# Sheet1.net
KiCad netlist of a schematic drawn in Altium Designer
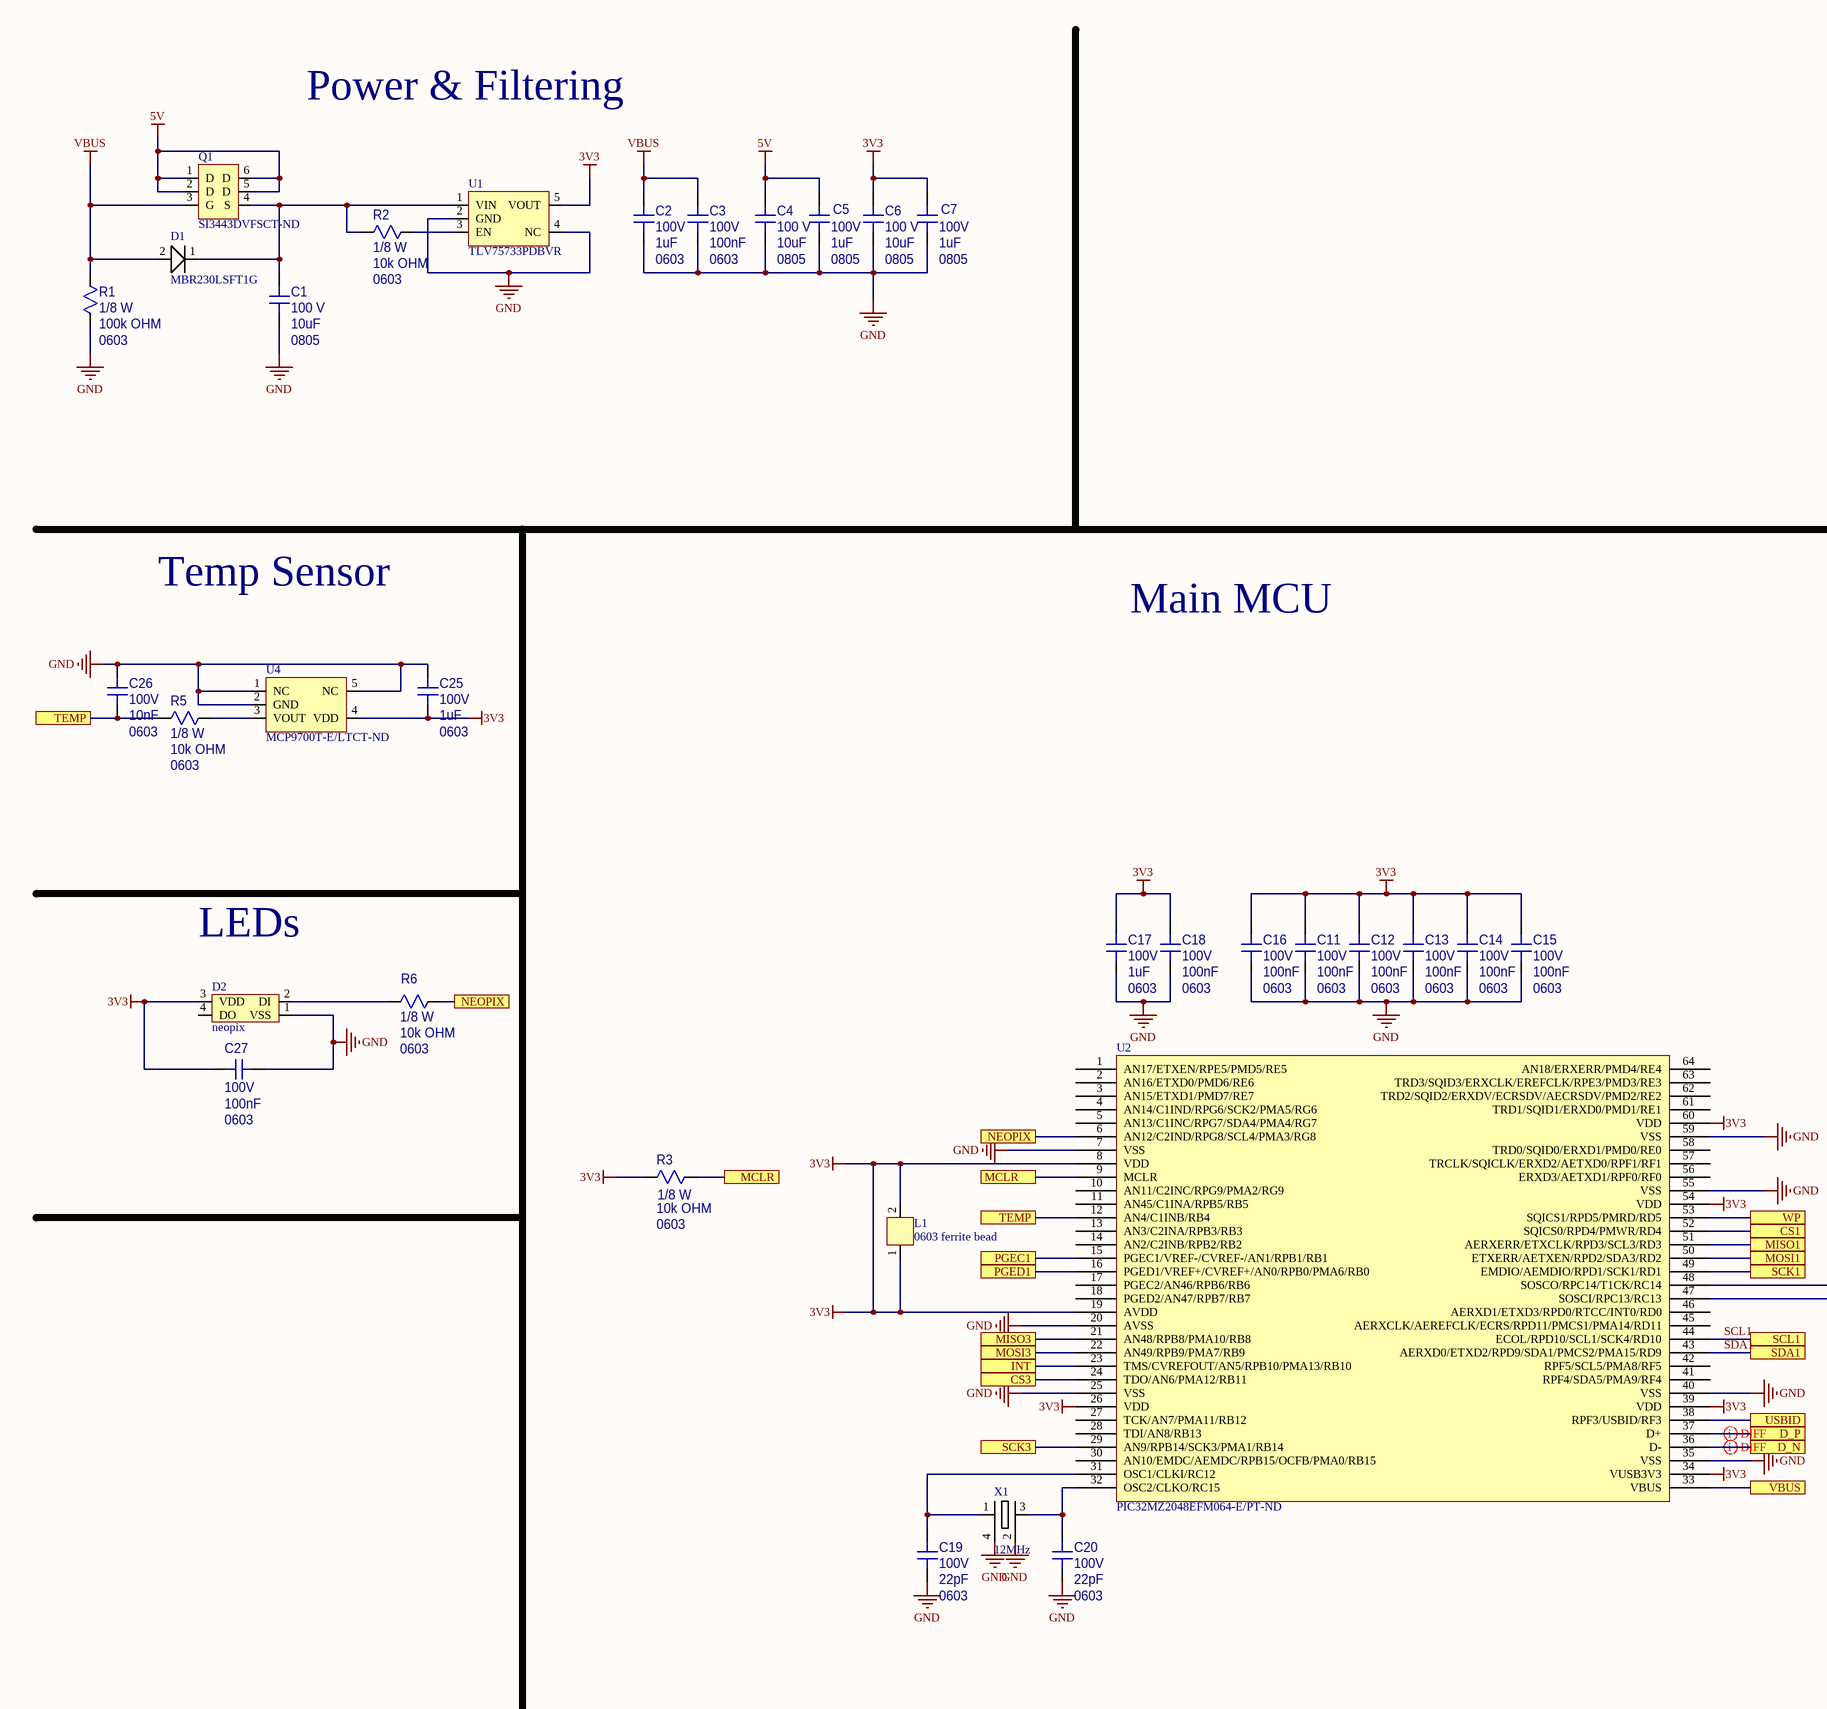
[diagram p0: Sheet1.SchDoc, left]
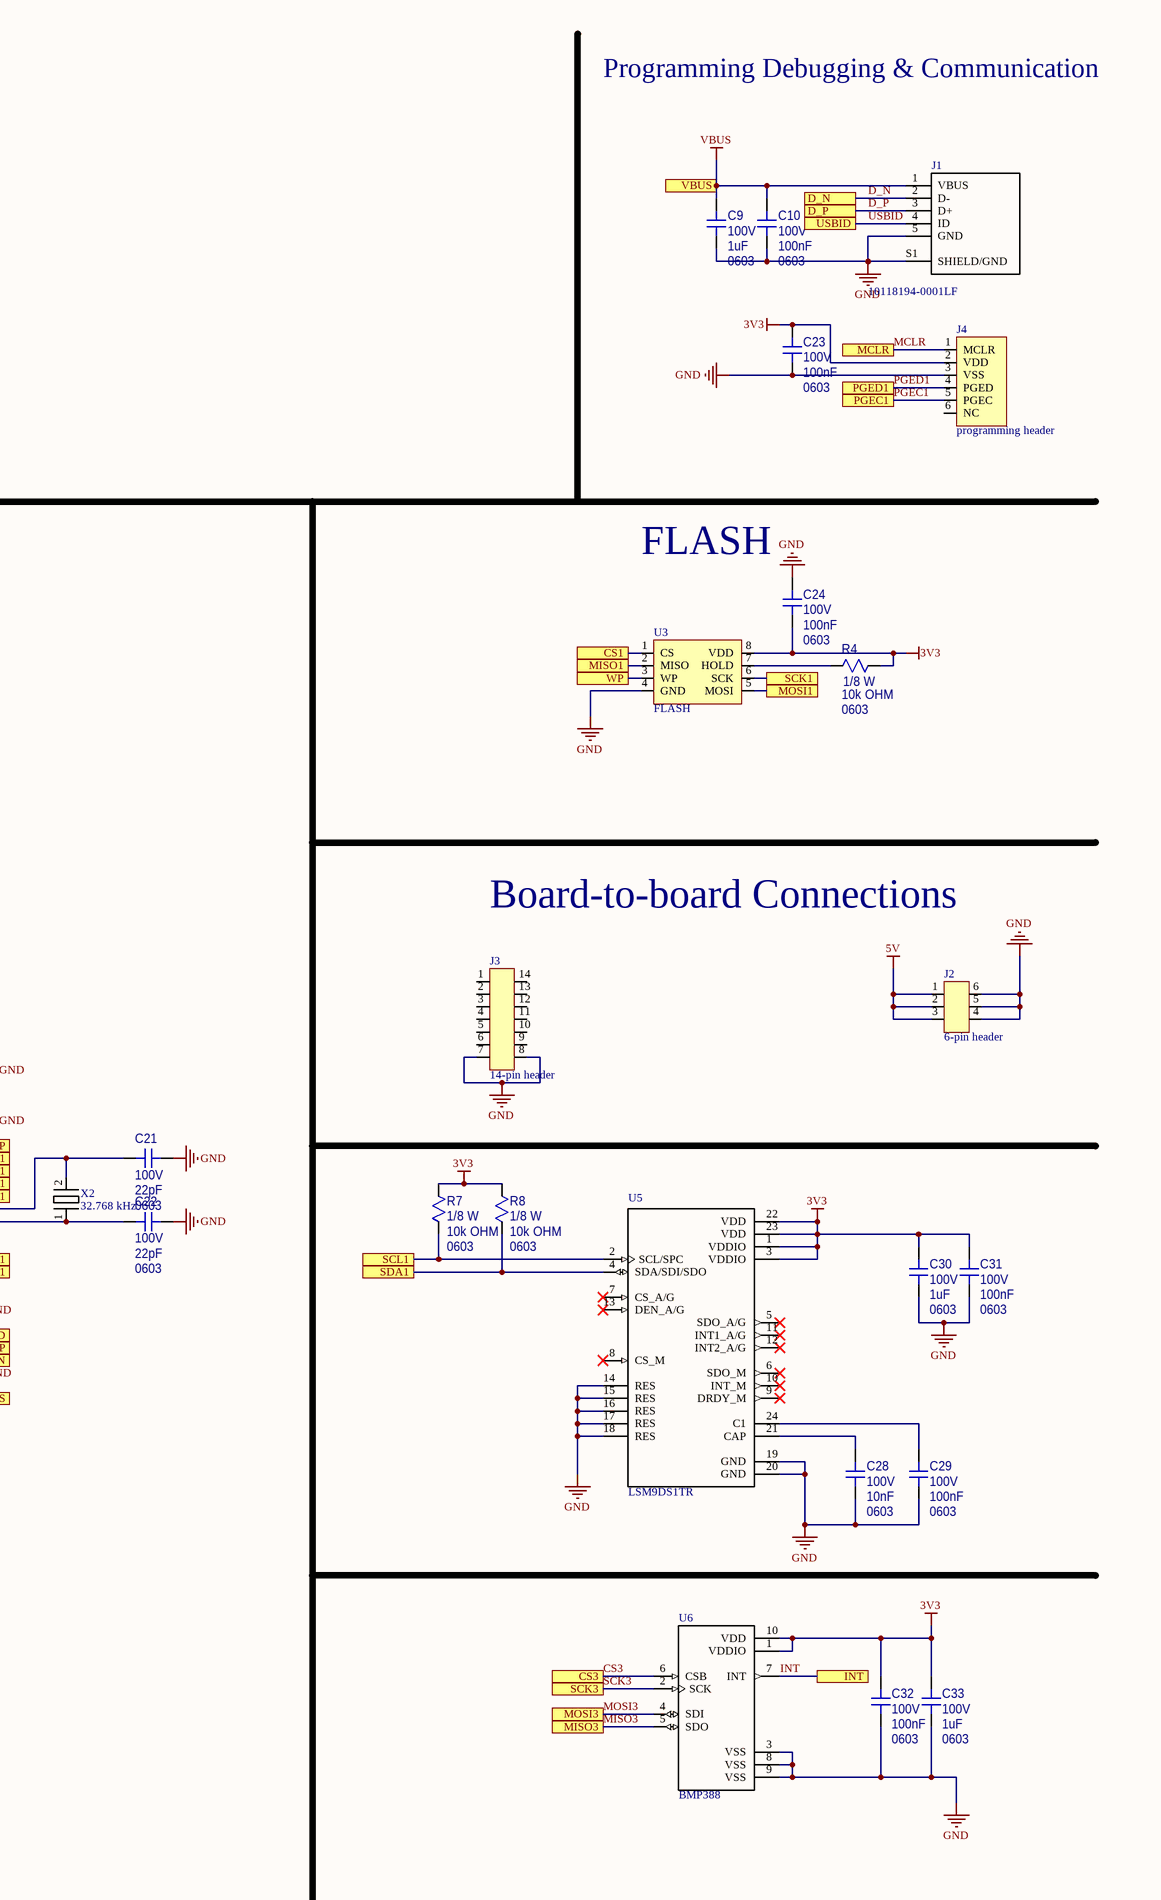
[diagram p1: Sheet1.SchDoc, right]

(export (version "E")
  (design (tool "Eeschema 10.0.6"))
  (components
    (comp (ref "C1")
      (value "10uF")
      (footprint "0805C (reflow)")
      (description "Default 0805 capacitor")
      (fields
        (field (name "VOLTAGE") "100 V")
        (field (name "SIZE") "0805")
        (field (name "Comment") "Capacitor")
      )
      (libsource (lib "rocket_mcu") (part "0805 Capacitor"))
    )
    (comp (ref "C2")
      (value "1uF")
      (footprint "0603C (reflow)")
      (description "Default 0603 capacitor")
      (fields
        (field (name "VOLTAGE") "100V")
        (field (name "SIZE") "0603")
        (field (name "Comment") "Capacitor")
      )
      (libsource (lib "rocket_mcu") (part "0603 Capacitor"))
    )
    (comp (ref "C3")
      (value "100nF")
      (footprint "0603C (reflow)")
      (description "Default 0603 capacitor")
      (fields
        (field (name "VOLTAGE") "100V")
        (field (name "SIZE") "0603")
        (field (name "Comment") "Capacitor")
      )
      (libsource (lib "rocket_mcu") (part "0603 Capacitor"))
    )
    (comp (ref "C4")
      (value "10uF")
      (footprint "0805C (reflow)")
      (description "Default 0805 capacitor")
      (fields
        (field (name "VOLTAGE") "100 V")
        (field (name "SIZE") "0805")
        (field (name "Comment") "Capacitor")
      )
      (libsource (lib "rocket_mcu") (part "0805 Capacitor"))
    )
    (comp (ref "C5")
      (value "1uF")
      (footprint "0805C (reflow)")
      (description "Default 0805 capacitor")
      (fields
        (field (name "VOLTAGE") "100V")
        (field (name "SIZE") "0805")
        (field (name "Comment") "Capacitor")
      )
      (libsource (lib "rocket_mcu") (part "0805 Capacitor"))
    )
    (comp (ref "C6")
      (value "10uF")
      (footprint "0805C (reflow)")
      (description "Default 0805 capacitor")
      (fields
        (field (name "VOLTAGE") "100 V")
        (field (name "SIZE") "0805")
        (field (name "Comment") "Capacitor")
      )
      (libsource (lib "rocket_mcu") (part "0805 Capacitor"))
    )
    (comp (ref "C7")
      (value "1uF")
      (footprint "0805C (reflow)")
      (description "Default 0805 capacitor")
      (fields
        (field (name "VOLTAGE") "100V")
        (field (name "SIZE") "0805")
        (field (name "Comment") "Capacitor")
      )
      (libsource (lib "rocket_mcu") (part "0805 Capacitor"))
    )
    (comp (ref "C9")
      (value "1uF")
      (footprint "0603C (reflow)")
      (description "Default 0603 capacitor")
      (fields
        (field (name "VOLTAGE") "100V")
        (field (name "SIZE") "0603")
        (field (name "Comment") "Capacitor")
      )
      (libsource (lib "rocket_mcu") (part "0603 Capacitor"))
    )
    (comp (ref "C10")
      (value "100nF")
      (footprint "0603C (reflow)")
      (description "Default 0603 capacitor")
      (fields
        (field (name "VOLTAGE") "100V")
        (field (name "SIZE") "0603")
        (field (name "Comment") "Capacitor")
      )
      (libsource (lib "rocket_mcu") (part "0603 Capacitor"))
    )
    (comp (ref "C11")
      (value "100nF")
      (footprint "0603C (reflow)")
      (description "Default 0603 capacitor")
      (fields
        (field (name "VOLTAGE") "100V")
        (field (name "SIZE") "0603")
        (field (name "Comment") "Capacitor")
      )
      (libsource (lib "rocket_mcu") (part "0603 Capacitor"))
    )
    (comp (ref "C12")
      (value "100nF")
      (footprint "0603C (reflow)")
      (description "Default 0603 capacitor")
      (fields
        (field (name "VOLTAGE") "100V")
        (field (name "SIZE") "0603")
        (field (name "Comment") "Capacitor")
      )
      (libsource (lib "rocket_mcu") (part "0603 Capacitor"))
    )
    (comp (ref "C13")
      (value "100nF")
      (footprint "0603C (reflow)")
      (description "Default 0603 capacitor")
      (fields
        (field (name "VOLTAGE") "100V")
        (field (name "SIZE") "0603")
        (field (name "Comment") "Capacitor")
      )
      (libsource (lib "rocket_mcu") (part "0603 Capacitor"))
    )
    (comp (ref "C14")
      (value "100nF")
      (footprint "0603C (reflow)")
      (description "Default 0603 capacitor")
      (fields
        (field (name "VOLTAGE") "100V")
        (field (name "SIZE") "0603")
        (field (name "Comment") "Capacitor")
      )
      (libsource (lib "rocket_mcu") (part "0603 Capacitor"))
    )
    (comp (ref "C15")
      (value "100nF")
      (footprint "0603C (reflow)")
      (description "Default 0603 capacitor")
      (fields
        (field (name "VOLTAGE") "100V")
        (field (name "SIZE") "0603")
        (field (name "Comment") "Capacitor")
      )
      (libsource (lib "rocket_mcu") (part "0603 Capacitor"))
    )
    (comp (ref "C16")
      (value "100nF")
      (footprint "0603C (reflow)")
      (description "Default 0603 capacitor")
      (fields
        (field (name "VOLTAGE") "100V")
        (field (name "SIZE") "0603")
        (field (name "Comment") "Capacitor")
      )
      (libsource (lib "rocket_mcu") (part "0603 Capacitor"))
    )
    (comp (ref "C17")
      (value "1uF")
      (footprint "0603C (reflow)")
      (description "Default 0603 capacitor")
      (fields
        (field (name "VOLTAGE") "100V")
        (field (name "SIZE") "0603")
        (field (name "Comment") "Capacitor")
      )
      (libsource (lib "rocket_mcu") (part "0603 Capacitor"))
    )
    (comp (ref "C18")
      (value "100nF")
      (footprint "0603C (reflow)")
      (description "Default 0603 capacitor")
      (fields
        (field (name "VOLTAGE") "100V")
        (field (name "SIZE") "0603")
        (field (name "Comment") "Capacitor")
      )
      (libsource (lib "rocket_mcu") (part "0603 Capacitor"))
    )
    (comp (ref "C19")
      (value "22pF")
      (footprint "0603C (reflow)")
      (description "Default 0603 capacitor")
      (fields
        (field (name "VOLTAGE") "100V")
        (field (name "SIZE") "0603")
        (field (name "Comment") "Capacitor")
      )
      (libsource (lib "rocket_mcu") (part "0603 Capacitor"))
    )
    (comp (ref "C20")
      (value "22pF")
      (footprint "0603C (reflow)")
      (description "Default 0603 capacitor")
      (fields
        (field (name "VOLTAGE") "100V")
        (field (name "SIZE") "0603")
        (field (name "Comment") "Capacitor")
      )
      (libsource (lib "rocket_mcu") (part "0603 Capacitor"))
    )
    (comp (ref "C21")
      (value "22pF")
      (footprint "0603C (reflow)")
      (description "Default 0603 capacitor")
      (fields
        (field (name "VOLTAGE") "100V")
        (field (name "SIZE") "0603")
        (field (name "Comment") "Capacitor")
      )
      (libsource (lib "rocket_mcu") (part "0603 Capacitor"))
    )
    (comp (ref "C22")
      (value "22pF")
      (footprint "0603C (reflow)")
      (description "Default 0603 capacitor")
      (fields
        (field (name "VOLTAGE") "100V")
        (field (name "SIZE") "0603")
        (field (name "Comment") "Capacitor")
      )
      (libsource (lib "rocket_mcu") (part "0603 Capacitor"))
    )
    (comp (ref "C23")
      (value "100nF")
      (footprint "0603C (reflow)")
      (description "Default 0603 capacitor")
      (fields
        (field (name "VOLTAGE") "100V")
        (field (name "SIZE") "0603")
        (field (name "Comment") "Capacitor")
      )
      (libsource (lib "rocket_mcu") (part "0603 Capacitor"))
    )
    (comp (ref "C24")
      (value "100nF")
      (footprint "0603C (reflow)")
      (description "Default 0603 capacitor")
      (fields
        (field (name "VOLTAGE") "100V")
        (field (name "SIZE") "0603")
        (field (name "Comment") "Capacitor")
      )
      (libsource (lib "rocket_mcu") (part "0603 Capacitor"))
    )
    (comp (ref "C25")
      (value "1uF")
      (footprint "0603C (reflow)")
      (description "Default 0603 capacitor")
      (fields
        (field (name "VOLTAGE") "100V")
        (field (name "SIZE") "0603")
        (field (name "Comment") "Capacitor")
      )
      (libsource (lib "rocket_mcu") (part "0603 Capacitor"))
    )
    (comp (ref "C26")
      (value "10nF")
      (footprint "0603C (reflow)")
      (description "Default 0603 capacitor")
      (fields
        (field (name "VOLTAGE") "100V")
        (field (name "SIZE") "0603")
        (field (name "Comment") "Capacitor")
      )
      (libsource (lib "rocket_mcu") (part "0603 Capacitor"))
    )
    (comp (ref "C27")
      (value "100nF")
      (footprint "0603C (reflow)")
      (description "Default 0603 capacitor")
      (fields
        (field (name "VOLTAGE") "100V")
        (field (name "SIZE") "0603")
        (field (name "Comment") "Capacitor")
      )
      (libsource (lib "rocket_mcu") (part "0603 Capacitor"))
    )
    (comp (ref "C28")
      (value "10nF")
      (footprint "0603C (reflow)")
      (description "Default 0603 capacitor")
      (fields
        (field (name "VOLTAGE") "100V")
        (field (name "SIZE") "0603")
        (field (name "Comment") "Capacitor")
      )
      (libsource (lib "rocket_mcu") (part "0603 Capacitor"))
    )
    (comp (ref "C29")
      (value "100nF")
      (footprint "0603C (reflow)")
      (description "Default 0603 capacitor")
      (fields
        (field (name "VOLTAGE") "100V")
        (field (name "SIZE") "0603")
        (field (name "Comment") "Capacitor")
      )
      (libsource (lib "rocket_mcu") (part "0603 Capacitor"))
    )
    (comp (ref "C30")
      (value "1uF")
      (footprint "0603C (reflow)")
      (description "Default 0603 capacitor")
      (fields
        (field (name "VOLTAGE") "100V")
        (field (name "SIZE") "0603")
        (field (name "Comment") "Capacitor")
      )
      (libsource (lib "rocket_mcu") (part "0603 Capacitor"))
    )
    (comp (ref "C31")
      (value "100nF")
      (footprint "0603C (reflow)")
      (description "Default 0603 capacitor")
      (fields
        (field (name "VOLTAGE") "100V")
        (field (name "SIZE") "0603")
        (field (name "Comment") "Capacitor")
      )
      (libsource (lib "rocket_mcu") (part "0603 Capacitor"))
    )
    (comp (ref "C32")
      (value "100nF")
      (footprint "0603C (reflow)")
      (description "Default 0603 capacitor")
      (fields
        (field (name "VOLTAGE") "100V")
        (field (name "SIZE") "0603")
        (field (name "Comment") "Capacitor")
      )
      (libsource (lib "rocket_mcu") (part "0603 Capacitor"))
    )
    (comp (ref "C33")
      (value "1uF")
      (footprint "0603C (reflow)")
      (description "Default 0603 capacitor")
      (fields
        (field (name "VOLTAGE") "100V")
        (field (name "SIZE") "0603")
        (field (name "Comment") "Capacitor")
      )
      (libsource (lib "rocket_mcu") (part "0603 Capacitor"))
    )
    (comp (ref "D1")
      (value "MBR230LSFT1G")
      (footprint "MBR230LSFT1G")
      (description "Schottky 30V 2A")
      (libsource (lib "rocket_mcu") (part "MBR230LSFT1G"))
    )
    (comp (ref "D2") (value "neopix") (footprint "neopix") (libsource (lib "rocket_mcu") (part "neopix")))
    (comp (ref "J1")
      (value "10118194-0001LF")
      (footprint "*AMPHENOL_10118194-0001LF_10118194-0001LF(Primary)")
      (description "USB - micro B USB 2.0 Receptacle Connector 5 Position Surface Mount, Right Angle; Through Hole")
      (fields (field (name "MF") "Amphenol ICC") (field (name "DIGI-KEY_PART_NUMBER") "609-4618-1-ND"))
      (libsource (lib "rocket_mcu") (part "10118194-0001LF"))
    )
    (comp (ref "J2")
      (value "6-pin header")
      (footprint "6-pin header")
      (libsource (lib "rocket_mcu") (part "6-pin header"))
    )
    (comp (ref "J3")
      (value "14-pin header")
      (footprint "14-pin header")
      (libsource (lib "rocket_mcu") (part "14-pin header"))
    )
    (comp (ref "J4")
      (value "programming header")
      (footprint "programming header")
      (libsource (lib "rocket_mcu") (part "programming header"))
    )
    (comp (ref "L1")
      (value "0603 ferrite bead")
      (footprint "0603R (reflow)")
      (libsource (lib "rocket_mcu") (part "0603 ferrite bead"))
    )
    (comp (ref "Q1")
      (value "SI3443DVFSCT-ND")
      (footprint "SI3443DVFSCT-ND")
      (libsource (lib "rocket_mcu") (part "SI3443DVFSCT-ND"))
    )
    (comp (ref "R1")
      (value "100k OHM")
      (footprint "0603R (reflow)")
      (description "Default 0603 resistor")
      (fields (field (name "POWER") "1/8 W") (field (name "SIZE") "0603") (field (name "Comment") "Resistor"))
      (libsource (lib "rocket_mcu") (part "0603 Resistor"))
    )
    (comp (ref "R2")
      (value "10k OHM")
      (footprint "0603R (reflow)")
      (description "Default 0603 resistor")
      (fields (field (name "POWER") "1/8 W") (field (name "SIZE") "0603") (field (name "Comment") "Resistor"))
      (libsource (lib "rocket_mcu") (part "0603 Resistor"))
    )
    (comp (ref "R3")
      (value "10k OHM")
      (footprint "0603R (reflow)")
      (description "Default 0603 resistor")
      (fields (field (name "POWER") "1/8 W") (field (name "SIZE") "0603") (field (name "Comment") "Resistor"))
      (libsource (lib "rocket_mcu") (part "0603 Resistor"))
    )
    (comp (ref "R4")
      (value "10k OHM")
      (footprint "0603R (reflow)")
      (description "Default 0603 resistor")
      (fields (field (name "POWER") "1/8 W") (field (name "SIZE") "0603") (field (name "Comment") "Resistor"))
      (libsource (lib "rocket_mcu") (part "0603 Resistor"))
    )
    (comp (ref "R5")
      (value "10k OHM")
      (footprint "0603R (reflow)")
      (description "Default 0603 resistor")
      (fields (field (name "POWER") "1/8 W") (field (name "SIZE") "0603") (field (name "Comment") "Resistor"))
      (libsource (lib "rocket_mcu") (part "0603 Resistor"))
    )
    (comp (ref "R6")
      (value "10k OHM")
      (footprint "0603R (reflow)")
      (description "Default 0603 resistor")
      (fields (field (name "POWER") "1/8 W") (field (name "SIZE") "0603") (field (name "Comment") "Resistor"))
      (libsource (lib "rocket_mcu") (part "0603 Resistor"))
    )
    (comp (ref "R7")
      (value "10k OHM")
      (footprint "0603R (reflow)")
      (description "Default 0603 resistor")
      (fields (field (name "POWER") "1/8 W") (field (name "SIZE") "0603") (field (name "Comment") "Resistor"))
      (libsource (lib "rocket_mcu") (part "0603 Resistor"))
    )
    (comp (ref "R8")
      (value "10k OHM")
      (footprint "0603R (reflow)")
      (description "Default 0603 resistor")
      (fields (field (name "POWER") "1/8 W") (field (name "SIZE") "0603") (field (name "Comment") "Resistor"))
      (libsource (lib "rocket_mcu") (part "0603 Resistor"))
    )
    (comp (ref "U1")
      (value "TLV75733PDBVR")
      (footprint "SOT23-5N")
      (libsource (lib "rocket_mcu") (part "TLV75733PDBVR"))
    )
    (comp (ref "U2")
      (value "PIC32MZ2048EFM064-E/PT-ND")
      (footprint "TQFP-64")
      (libsource (lib "rocket_mcu") (part "PIC32MZ2048EFM064-E/PT-ND"))
    )
    (comp (ref "U3") (value "FLASH") (footprint "8-SOIC") (libsource (lib "rocket_mcu") (part "MB85RS64V")))
    (comp (ref "U4")
      (value "MCP9700T-E/LTCT-ND")
      (footprint "MCP9700T-E/LT")
      (description "Temp sens")
      (libsource (lib "rocket_mcu") (part "MCP9700T-E/LTCT-ND"))
    )
    (comp (ref "U5")
      (value "LSM9DS1TR")
      (footprint "*PQFN43P300X350X102-24N")
      (description "Accelerometer, Gyroscope, Magnetometer, Temperature, 9 Axis Sensor I虏C, SPI Output")
      (fields (field (name "DIGI-KEY_PART_NUMBER") "497-14946-1-ND") (field (name "MF") "STMicroelectronics"))
      (libsource (lib "rocket_mcu") (part "LSM9DS1TR"))
    )
    (comp (ref "U6")
      (value "BMP388")
      (footprint "*PQFN50P200X200X80-10N")
      (description "Pressure Sensor 4.35PSI ~ 18.13PSI _30kPa ~ 125kPa_ Absolute 10-WFLGA")
      (fields (field (name "MF") "Bosch Sensortec") (field (name "DIGI-KEY_PART_NUMBER") "828-1079-1-ND"))
      (libsource (lib "rocket_mcu") (part "BMP388"))
    )
    (comp (ref "X1")
      (value "12MHz")
      (footprint "XC2731CT-ND")
      (libsource (lib "rocket_mcu") (part "XC2731CT-ND"))
    )
    (comp (ref "X2")
      (value "32.768 kHz")
      (footprint "XC2292CT-ND")
      (libsource (lib "rocket_mcu") (part "XC2292CT-ND"))
    )
  )
  (nets
    (net (code "1") (name "/CS1") (class "Default")
      (node (ref "U2") (pin "52") (pinfunction "SQICS0/RPD4/PMWR/RD4_52") (pintype "passive"))
      (node (ref "U3") (pin "1") (pinfunction "CS_1") (pintype "passive"))
    )
    (net (code "2") (name "/CS3") (class "Default")
      (node (ref "U2") (pin "24") (pinfunction "TDO/AN6/PMA12/RB11_24") (pintype "passive"))
      (node (ref "U6") (pin "6") (pinfunction "CSB_6") (pintype "input"))
    )
    (net (code "3") (name "/D_N") (class "Default")
      (node (ref "J1") (pin "2") (pinfunction "D-_2") (pintype "passive"))
      (node (ref "U2") (pin "36") (pinfunction "D-_36") (pintype "passive"))
    )
    (net (code "4") (name "/D_P") (class "Default")
      (node (ref "J1") (pin "3") (pinfunction "D+_3") (pintype "passive"))
      (node (ref "U2") (pin "37") (pinfunction "D+_37") (pintype "passive"))
    )
    (net (code "5") (name "/INT") (class "Default")
      (node (ref "U2") (pin "23") (pinfunction "TMS/CVREFOUT/AN5/RPB10/PMA13/RB10_23") (pintype "passive"))
      (node (ref "U6") (pin "7") (pinfunction "INT_7") (pintype "output"))
    )
    (net (code "6") (name "/MCLR") (class "Default")
      (node (ref "J4") (pin "1") (pinfunction "MCLR_1") (pintype "passive"))
      (node (ref "R3") (pin "2") (pintype "passive"))
      (node (ref "U2") (pin "9") (pinfunction "MCLR_9") (pintype "passive"))
    )
    (net (code "7") (name "/MISO1") (class "Default")
      (node (ref "U2") (pin "51") (pinfunction "AERXERR/ETXCLK/RPD3/SCL3/RD3_51") (pintype "passive"))
      (node (ref "U3") (pin "2") (pinfunction "MISO_2") (pintype "passive"))
    )
    (net (code "8") (name "/MISO3") (class "Default")
      (node (ref "U2") (pin "21") (pinfunction "AN48/RPB8/PMA10/RB8_21") (pintype "passive"))
      (node (ref "U6") (pin "5") (pinfunction "SDO_5") (pintype "bidirectional"))
    )
    (net (code "9") (name "/MOSI1") (class "Default")
      (node (ref "U2") (pin "50") (pinfunction "ETXERR/AETXEN/RPD2/SDA3/RD2_50") (pintype "passive"))
      (node (ref "U3") (pin "5") (pinfunction "MOSI_5") (pintype "passive"))
    )
    (net (code "10") (name "/MOSI3") (class "Default")
      (node (ref "U2") (pin "22") (pinfunction "AN49/RPB9/PMA7/RB9_22") (pintype "passive"))
      (node (ref "U6") (pin "4") (pinfunction "SDI_4") (pintype "bidirectional"))
    )
    (net (code "11") (name "/NEOPIX") (class "Default")
      (node (ref "R6") (pin "1") (pintype "passive"))
      (node (ref "U2") (pin "6") (pinfunction "AN12/C2IND/RPG8/SCL4/PMA3/RG8_6") (pintype "passive"))
    )
    (net (code "12") (name "/PGEC1") (class "Default")
      (node (ref "J4") (pin "5") (pinfunction "PGEC_5") (pintype "passive"))
      (node (ref "U2") (pin "15") (pinfunction "PGEC1/VREF-/CVREF-/AN1/RPB1/RB1_15") (pintype "passive"))
    )
    (net (code "13") (name "/PGED1") (class "Default")
      (node (ref "J4") (pin "4") (pinfunction "PGED_4") (pintype "passive"))
      (node (ref "U2") (pin "16") (pinfunction "PGED1/VREF+/CVREF+/AN0/RPB0/PMA6/RB0_16") (pintype "passive"))
    )
    (net (code "14") (name "/SCK1") (class "Default")
      (node (ref "U2") (pin "49") (pinfunction "EMDIO/AEMDIO/RPD1/SCK1/RD1_49") (pintype "passive"))
      (node (ref "U3") (pin "6") (pinfunction "SCK_6") (pintype "passive"))
    )
    (net (code "15") (name "/SCK3") (class "Default")
      (node (ref "U2") (pin "29") (pinfunction "AN9/RPB14/SCK3/PMA1/RB14_29") (pintype "passive"))
      (node (ref "U6") (pin "2") (pinfunction "SCK_2") (pintype "input"))
    )
    (net (code "16") (name "/SCL1") (class "Default")
      (node (ref "R7") (pin "1") (pintype "passive"))
      (node (ref "U2") (pin "44") (pinfunction "ECOL/RPD10/SCL1/SCK4/RD10_44") (pintype "passive"))
      (node (ref "U5") (pin "2") (pinfunction "SCL/SPC_2") (pintype "input"))
    )
    (net (code "17") (name "/SDA1") (class "Default")
      (node (ref "R8") (pin "1") (pintype "passive"))
      (node (ref "U2") (pin "43") (pinfunction "AERXD0/ETXD2/RPD9/SDA1/PMCS2/PMA15/RD9_43") (pintype "passive"))
      (node (ref "U5") (pin "4") (pinfunction "SDA/SDI/SDO_4") (pintype "bidirectional"))
    )
    (net (code "18") (name "/TEMP") (class "Default")
      (node (ref "C26") (pin "2") (pintype "passive"))
      (node (ref "R5") (pin "2") (pintype "passive"))
      (node (ref "U2") (pin "12") (pinfunction "AN4/C1INB/RB4_12") (pintype "passive"))
    )
    (net (code "19") (name "/USBID") (class "Default")
      (node (ref "J1") (pin "4") (pinfunction "ID_4") (pintype "passive"))
      (node (ref "U2") (pin "38") (pinfunction "RPF3/USBID/RF3_38") (pintype "passive"))
    )
    (net (code "20") (name "/WP") (class "Default")
      (node (ref "U2") (pin "53") (pinfunction "SQICS1/RPD5/PMRD/RD5_53") (pintype "passive"))
      (node (ref "U3") (pin "3") (pinfunction "WP_3") (pintype "passive"))
    )
    (net (code "21") (name "3V3") (class "Default")
      (node (ref "C11") (pin "1") (pintype "passive"))
      (node (ref "C12") (pin "1") (pintype "passive"))
      (node (ref "C13") (pin "1") (pintype "passive"))
      (node (ref "C14") (pin "1") (pintype "passive"))
      (node (ref "C15") (pin "1") (pintype "passive"))
      (node (ref "C16") (pin "1") (pintype "passive"))
      (node (ref "C17") (pin "1") (pintype "passive"))
      (node (ref "C18") (pin "1") (pintype "passive"))
      (node (ref "C23") (pin "1") (pintype "passive"))
      (node (ref "C24") (pin "2") (pintype "passive"))
      (node (ref "C25") (pin "2") (pintype "passive"))
      (node (ref "C27") (pin "1") (pintype "passive"))
      (node (ref "C30") (pin "1") (pintype "passive"))
      (node (ref "C31") (pin "2") (pintype "passive"))
      (node (ref "C32") (pin "2") (pintype "passive"))
      (node (ref "C33") (pin "2") (pintype "passive"))
      (node (ref "C6") (pin "1") (pintype "passive"))
      (node (ref "C7") (pin "1") (pintype "passive"))
      (node (ref "D2") (pin "3") (pinfunction "VDD_3") (pintype "passive"))
      (node (ref "J4") (pin "2") (pinfunction "VDD_2") (pintype "passive"))
      (node (ref "L1") (pin "1") (pinfunction "1_1") (pintype "passive"))
      (node (ref "L1") (pin "2") (pinfunction "2_2") (pintype "passive"))
      (node (ref "R3") (pin "1") (pintype "passive"))
      (node (ref "R4") (pin "2") (pintype "passive"))
      (node (ref "R7") (pin "2") (pintype "passive"))
      (node (ref "R8") (pin "2") (pintype "passive"))
      (node (ref "U1") (pin "5") (pinfunction "VOUT_5") (pintype "passive"))
      (node (ref "U2") (pin "19") (pinfunction "AVDD_19") (pintype "passive"))
      (node (ref "U2") (pin "26") (pinfunction "VDD_26") (pintype "passive"))
      (node (ref "U2") (pin "34") (pinfunction "VUSB3V3_34") (pintype "passive"))
      (node (ref "U2") (pin "39") (pinfunction "VDD_39") (pintype "passive"))
      (node (ref "U2") (pin "54") (pinfunction "VDD_54") (pintype "passive"))
      (node (ref "U2") (pin "60") (pinfunction "VDD_60") (pintype "passive"))
      (node (ref "U2") (pin "8") (pinfunction "VDD_8") (pintype "passive"))
      (node (ref "U3") (pin "8") (pinfunction "VDD_8") (pintype "passive"))
      (node (ref "U4") (pin "4") (pinfunction "VDD_4") (pintype "passive"))
      (node (ref "U5") (pin "1") (pinfunction "VDDIO_1") (pintype "power_in"))
      (node (ref "U5") (pin "22") (pinfunction "VDD_22") (pintype "power_in"))
      (node (ref "U5") (pin "23") (pinfunction "VDD_23") (pintype "power_in"))
      (node (ref "U5") (pin "3") (pinfunction "VDDIO_3") (pintype "power_in"))
      (node (ref "U6") (pin "1") (pinfunction "VDDIO_1") (pintype "power_in"))
      (node (ref "U6") (pin "10") (pinfunction "VDD_10") (pintype "power_in"))
    )
    (net (code "22") (name "5V") (class "Default")
      (node (ref "C4") (pin "1") (pintype "passive"))
      (node (ref "C5") (pin "1") (pintype "passive"))
      (node (ref "J2") (pin "1") (pinfunction "1_1") (pintype "passive"))
      (node (ref "J2") (pin "2") (pinfunction "2_2") (pintype "passive"))
      (node (ref "J2") (pin "3") (pinfunction "3_3") (pintype "passive"))
      (node (ref "Q1") (pin "1") (pinfunction "D_1") (pintype "passive"))
      (node (ref "Q1") (pin "2") (pinfunction "D_2") (pintype "passive"))
      (node (ref "Q1") (pin "5") (pinfunction "D_5") (pintype "passive"))
      (node (ref "Q1") (pin "6") (pinfunction "D_6") (pintype "passive"))
    )
    (net (code "23") (name "GND") (class "Default")
      (node (ref "C1") (pin "2") (pintype "passive"))
      (node (ref "C10") (pin "2") (pintype "passive"))
      (node (ref "C11") (pin "2") (pintype "passive"))
      (node (ref "C12") (pin "2") (pintype "passive"))
      (node (ref "C13") (pin "2") (pintype "passive"))
      (node (ref "C14") (pin "2") (pintype "passive"))
      (node (ref "C15") (pin "2") (pintype "passive"))
      (node (ref "C16") (pin "2") (pintype "passive"))
      (node (ref "C17") (pin "2") (pintype "passive"))
      (node (ref "C18") (pin "2") (pintype "passive"))
      (node (ref "C19") (pin "2") (pintype "passive"))
      (node (ref "C2") (pin "2") (pintype "passive"))
      (node (ref "C20") (pin "2") (pintype "passive"))
      (node (ref "C21") (pin "2") (pintype "passive"))
      (node (ref "C22") (pin "2") (pintype "passive"))
      (node (ref "C23") (pin "2") (pintype "passive"))
      (node (ref "C24") (pin "1") (pintype "passive"))
      (node (ref "C25") (pin "1") (pintype "passive"))
      (node (ref "C26") (pin "1") (pintype "passive"))
      (node (ref "C27") (pin "2") (pintype "passive"))
      (node (ref "C28") (pin "1") (pintype "passive"))
      (node (ref "C29") (pin "1") (pintype "passive"))
      (node (ref "C3") (pin "2") (pintype "passive"))
      (node (ref "C30") (pin "2") (pintype "passive"))
      (node (ref "C31") (pin "1") (pintype "passive"))
      (node (ref "C32") (pin "1") (pintype "passive"))
      (node (ref "C33") (pin "1") (pintype "passive"))
      (node (ref "C4") (pin "2") (pintype "passive"))
      (node (ref "C5") (pin "2") (pintype "passive"))
      (node (ref "C6") (pin "2") (pintype "passive"))
      (node (ref "C7") (pin "2") (pintype "passive"))
      (node (ref "C9") (pin "2") (pintype "passive"))
      (node (ref "D2") (pin "1") (pinfunction "VSS_1") (pintype "passive"))
      (node (ref "J1") (pin "5") (pinfunction "GND_5") (pintype "passive"))
      (node (ref "J1") (pin "S1") (pinfunction "SHIELD/GND_S1") (pintype "passive"))
      (node (ref "J2") (pin "4") (pinfunction "4_4") (pintype "passive"))
      (node (ref "J2") (pin "5") (pinfunction "5_5") (pintype "passive"))
      (node (ref "J2") (pin "6") (pinfunction "6_6") (pintype "passive"))
      (node (ref "J3") (pin "7") (pinfunction "7_7") (pintype "passive"))
      (node (ref "J3") (pin "8") (pinfunction "8_8") (pintype "passive"))
      (node (ref "J4") (pin "3") (pinfunction "VSS_3") (pintype "passive"))
      (node (ref "R1") (pin "1") (pintype "passive"))
      (node (ref "U1") (pin "2") (pinfunction "GND_2") (pintype "passive"))
      (node (ref "U1") (pin "4") (pinfunction "NC_4") (pintype "passive"))
      (node (ref "U2") (pin "20") (pinfunction "AVSS_20") (pintype "passive"))
      (node (ref "U2") (pin "25") (pinfunction "VSS_25") (pintype "passive"))
      (node (ref "U2") (pin "35") (pinfunction "VSS_35") (pintype "passive"))
      (node (ref "U2") (pin "40") (pinfunction "VSS_40") (pintype "passive"))
      (node (ref "U2") (pin "55") (pinfunction "VSS_55") (pintype "passive"))
      (node (ref "U2") (pin "59") (pinfunction "VSS_59") (pintype "passive"))
      (node (ref "U2") (pin "7") (pinfunction "VSS_7") (pintype "passive"))
      (node (ref "U3") (pin "4") (pinfunction "GND_4") (pintype "passive"))
      (node (ref "U4") (pin "1") (pinfunction "NC_1") (pintype "passive"))
      (node (ref "U4") (pin "2") (pinfunction "GND_2") (pintype "passive"))
      (node (ref "U4") (pin "5") (pinfunction "NC_5") (pintype "passive"))
      (node (ref "U5") (pin "14") (pinfunction "RES_14") (pintype "passive"))
      (node (ref "U5") (pin "15") (pinfunction "RES_15") (pintype "passive"))
      (node (ref "U5") (pin "16") (pinfunction "RES_16") (pintype "passive"))
      (node (ref "U5") (pin "17") (pinfunction "RES_17") (pintype "passive"))
      (node (ref "U5") (pin "18") (pinfunction "RES_18") (pintype "passive"))
      (node (ref "U5") (pin "19") (pinfunction "GND_19") (pintype "power_in"))
      (node (ref "U5") (pin "20") (pinfunction "GND_20") (pintype "power_in"))
      (node (ref "U6") (pin "3") (pinfunction "VSS_3") (pintype "power_in"))
      (node (ref "U6") (pin "8") (pinfunction "VSS_8") (pintype "power_in"))
      (node (ref "U6") (pin "9") (pinfunction "VSS_9") (pintype "power_in"))
      (node (ref "X1") (pin "2") (pinfunction "2_2") (pintype "passive"))
      (node (ref "X1") (pin "4") (pinfunction "4_4") (pintype "passive"))
    )
    (net (code "24") (name "Net-(D2-DI)") (class "Default")
      (node (ref "D2") (pin "2") (pinfunction "DI_2") (pintype "passive"))
      (node (ref "R6") (pin "2") (pintype "passive"))
    )
    (net (code "25") (name "Net-(Q1-S)") (class "Default")
      (node (ref "C1") (pin "1") (pintype "passive"))
      (node (ref "D1") (pin "1") (pinfunction "1_1") (pintype "passive"))
      (node (ref "Q1") (pin "4") (pinfunction "S_4") (pintype "passive"))
      (node (ref "R2") (pin "2") (pintype "passive"))
      (node (ref "U1") (pin "1") (pinfunction "VIN_1") (pintype "passive"))
    )
    (net (code "26") (name "Net-(U1-EN)") (class "Default")
      (node (ref "R2") (pin "1") (pintype "passive"))
      (node (ref "U1") (pin "3") (pinfunction "EN_3") (pintype "passive"))
    )
    (net (code "27") (name "Net-(U2-OSC1{slash}CLKI{slash}RC12)") (class "Default")
      (node (ref "C19") (pin "1") (pintype "passive"))
      (node (ref "U2") (pin "31") (pinfunction "OSC1/CLKI/RC12_31") (pintype "passive"))
      (node (ref "X1") (pin "1") (pinfunction "1_1") (pintype "passive"))
    )
    (net (code "28") (name "Net-(U2-OSC2{slash}CLKO{slash}RC15)") (class "Default")
      (node (ref "C20") (pin "1") (pintype "passive"))
      (node (ref "U2") (pin "32") (pinfunction "OSC2/CLKO/RC15_32") (pintype "passive"))
      (node (ref "X1") (pin "3") (pinfunction "3_3") (pintype "passive"))
    )
    (net (code "29") (name "Net-(U2-SOSCI{slash}RPC13{slash}RC13)") (class "Default")
      (node (ref "C22") (pin "1") (pintype "passive"))
      (node (ref "U2") (pin "47") (pinfunction "SOSCI/RPC13/RC13_47") (pintype "passive"))
      (node (ref "X2") (pin "1") (pinfunction "1_1") (pintype "passive"))
    )
    (net (code "30") (name "Net-(U2-SOSCO{slash}RPC14{slash}T1CK{slash}RC14)") (class "Default")
      (node (ref "C21") (pin "1") (pintype "passive"))
      (node (ref "U2") (pin "48") (pinfunction "SOSCO/RPC14/T1CK/RC14_48") (pintype "passive"))
      (node (ref "X2") (pin "2") (pinfunction "2_2") (pintype "passive"))
    )
    (net (code "31") (name "Net-(U3-HOLD)") (class "Default")
      (node (ref "R4") (pin "1") (pintype "passive"))
      (node (ref "U3") (pin "7") (pinfunction "HOLD_7") (pintype "passive"))
    )
    (net (code "32") (name "Net-(U4-VOUT)") (class "Default")
      (node (ref "R5") (pin "1") (pintype "passive"))
      (node (ref "U4") (pin "3") (pinfunction "VOUT_3") (pintype "passive"))
    )
    (net (code "33") (name "Net-(U5-C1)") (class "Default")
      (node (ref "C29") (pin "2") (pintype "passive"))
      (node (ref "U5") (pin "24") (pinfunction "C1_24") (pintype "passive"))
    )
    (net (code "34") (name "Net-(U5-CAP)") (class "Default")
      (node (ref "C28") (pin "2") (pintype "passive"))
      (node (ref "U5") (pin "21") (pinfunction "CAP_21") (pintype "passive"))
    )
    (net (code "35") (name "VBUS") (class "Default")
      (node (ref "C10") (pin "1") (pintype "passive"))
      (node (ref "C2") (pin "1") (pintype "passive"))
      (node (ref "C3") (pin "1") (pintype "passive"))
      (node (ref "C9") (pin "1") (pintype "passive"))
      (node (ref "D1") (pin "2") (pinfunction "2_2") (pintype "passive"))
      (node (ref "J1") (pin "1") (pinfunction "VBUS_1") (pintype "passive"))
      (node (ref "Q1") (pin "3") (pinfunction "G_3") (pintype "passive"))
      (node (ref "R1") (pin "2") (pintype "passive"))
      (node (ref "U2") (pin "33") (pinfunction "VBUS_33") (pintype "passive"))
    )
    (net (code "36") (name "unconnected-(D2-DO-Pad4)") (class "Default")
      (node (ref "D2") (pin "4") (pinfunction "DO_4") (pintype "passive"))
    )
    (net (code "37") (name "unconnected-(J3-Pad1)") (class "Default")
      (node (ref "J3") (pin "1") (pinfunction "1_1") (pintype "passive"))
    )
    (net (code "38") (name "unconnected-(J3-Pad2)") (class "Default")
      (node (ref "J3") (pin "2") (pinfunction "2_2") (pintype "passive"))
    )
    (net (code "39") (name "unconnected-(J3-Pad3)") (class "Default")
      (node (ref "J3") (pin "3") (pinfunction "3_3") (pintype "passive"))
    )
    (net (code "40") (name "unconnected-(J3-Pad4)") (class "Default")
      (node (ref "J3") (pin "4") (pinfunction "4_4") (pintype "passive"))
    )
    (net (code "41") (name "unconnected-(J3-Pad5)") (class "Default")
      (node (ref "J3") (pin "5") (pinfunction "5_5") (pintype "passive"))
    )
    (net (code "42") (name "unconnected-(J3-Pad6)") (class "Default")
      (node (ref "J3") (pin "6") (pinfunction "6_6") (pintype "passive"))
    )
    (net (code "43") (name "unconnected-(J3-Pad9)") (class "Default")
      (node (ref "J3") (pin "9") (pinfunction "9_9") (pintype "passive"))
    )
    (net (code "44") (name "unconnected-(J3-Pad10)") (class "Default")
      (node (ref "J3") (pin "10") (pinfunction "10_10") (pintype "passive"))
    )
    (net (code "45") (name "unconnected-(J3-Pad11)") (class "Default")
      (node (ref "J3") (pin "11") (pinfunction "11_11") (pintype "passive"))
    )
    (net (code "46") (name "unconnected-(J3-Pad12)") (class "Default")
      (node (ref "J3") (pin "12") (pinfunction "12_12") (pintype "passive"))
    )
    (net (code "47") (name "unconnected-(J3-Pad13)") (class "Default")
      (node (ref "J3") (pin "13") (pinfunction "13_13") (pintype "passive"))
    )
    (net (code "48") (name "unconnected-(J3-Pad14)") (class "Default")
      (node (ref "J3") (pin "14") (pinfunction "14_14") (pintype "passive"))
    )
    (net (code "49") (name "unconnected-(J4-NC-Pad6)") (class "Default")
      (node (ref "J4") (pin "6") (pinfunction "NC_6") (pintype "passive"))
    )
    (net (code "50") (name "unconnected-(U2-AERXCLK{slash}AEREFCLK{slash}ECRS{slash}RPD11{slash}PMCS1{slash}PMA14{slash}RD11-Pad45)") (class "Default")
      (node (ref "U2") (pin "45") (pinfunction "AERXCLK/AEREFCLK/ECRS/RPD11/PMCS1/PMA14/RD11_45") (pintype "passive"))
    )
    (net (code "51") (name "unconnected-(U2-AERXD1{slash}ETXD3{slash}RPD0{slash}RTCC{slash}INT0{slash}RD0-Pad46)") (class "Default")
      (node (ref "U2") (pin "46") (pinfunction "AERXD1/ETXD3/RPD0/RTCC/INT0/RD0_46") (pintype "passive"))
    )
    (net (code "52") (name "unconnected-(U2-AN2{slash}C2INB{slash}RPB2{slash}RB2-Pad14)") (class "Default")
      (node (ref "U2") (pin "14") (pinfunction "AN2/C2INB/RPB2/RB2_14") (pintype "passive"))
    )
    (net (code "53") (name "unconnected-(U2-AN3{slash}C2INA{slash}RPB3{slash}RB3-Pad13)") (class "Default")
      (node (ref "U2") (pin "13") (pinfunction "AN3/C2INA/RPB3/RB3_13") (pintype "passive"))
    )
    (net (code "54") (name "unconnected-(U2-AN10{slash}EMDC{slash}AEMDC{slash}RPB15{slash}OCFB{slash}PMA0{slash}RB15-Pad30)") (class "Default")
      (node (ref "U2") (pin "30") (pinfunction "AN10/EMDC/AEMDC/RPB15/OCFB/PMA0/RB15_30") (pintype "passive"))
    )
    (net (code "55") (name "unconnected-(U2-AN11{slash}C2INC{slash}RPG9{slash}PMA2{slash}RG9-Pad10)") (class "Default")
      (node (ref "U2") (pin "10") (pinfunction "AN11/C2INC/RPG9/PMA2/RG9_10") (pintype "passive"))
    )
    (net (code "56") (name "unconnected-(U2-AN13{slash}C1INC{slash}RPG7{slash}SDA4{slash}PMA4{slash}RG7-Pad5)") (class "Default")
      (node (ref "U2") (pin "5") (pinfunction "AN13/C1INC/RPG7/SDA4/PMA4/RG7_5") (pintype "passive"))
    )
    (net (code "57") (name "unconnected-(U2-AN14{slash}C1IND{slash}RPG6{slash}SCK2{slash}PMA5{slash}RG6-Pad4)") (class "Default")
      (node (ref "U2") (pin "4") (pinfunction "AN14/C1IND/RPG6/SCK2/PMA5/RG6_4") (pintype "passive"))
    )
    (net (code "58") (name "unconnected-(U2-AN15{slash}ETXD1{slash}PMD7{slash}RE7-Pad3)") (class "Default")
      (node (ref "U2") (pin "3") (pinfunction "AN15/ETXD1/PMD7/RE7_3") (pintype "passive"))
    )
    (net (code "59") (name "unconnected-(U2-AN16{slash}ETXD0{slash}PMD6{slash}RE6-Pad2)") (class "Default")
      (node (ref "U2") (pin "2") (pinfunction "AN16/ETXD0/PMD6/RE6_2") (pintype "passive"))
    )
    (net (code "60") (name "unconnected-(U2-AN17{slash}ETXEN{slash}RPE5{slash}PMD5{slash}RE5-Pad1)") (class "Default")
      (node (ref "U2") (pin "1") (pinfunction "AN17/ETXEN/RPE5/PMD5/RE5_1") (pintype "passive"))
    )
    (net (code "61") (name "unconnected-(U2-AN18{slash}ERXERR{slash}PMD4{slash}RE4-Pad64)") (class "Default")
      (node (ref "U2") (pin "64") (pinfunction "AN18/ERXERR/PMD4/RE4_64") (pintype "passive"))
    )
    (net (code "62") (name "unconnected-(U2-AN45{slash}C1INA{slash}RPB5{slash}RB5-Pad11)") (class "Default")
      (node (ref "U2") (pin "11") (pinfunction "AN45/C1INA/RPB5/RB5_11") (pintype "passive"))
    )
    (net (code "63") (name "unconnected-(U2-ERXD3{slash}AETXD1{slash}RPF0{slash}RF0-Pad56)") (class "Default")
      (node (ref "U2") (pin "56") (pinfunction "ERXD3/AETXD1/RPF0/RF0_56") (pintype "passive"))
    )
    (net (code "64") (name "unconnected-(U2-PGEC2{slash}AN46{slash}RPB6{slash}RB6-Pad17)") (class "Default")
      (node (ref "U2") (pin "17") (pinfunction "PGEC2/AN46/RPB6/RB6_17") (pintype "passive"))
    )
    (net (code "65") (name "unconnected-(U2-PGED2{slash}AN47{slash}RPB7{slash}RB7-Pad18)") (class "Default")
      (node (ref "U2") (pin "18") (pinfunction "PGED2/AN47/RPB7/RB7_18") (pintype "passive"))
    )
    (net (code "66") (name "unconnected-(U2-RPF4{slash}SDA5{slash}PMA9{slash}RF4-Pad41)") (class "Default")
      (node (ref "U2") (pin "41") (pinfunction "RPF4/SDA5/PMA9/RF4_41") (pintype "passive"))
    )
    (net (code "67") (name "unconnected-(U2-RPF5{slash}SCL5{slash}PMA8{slash}RF5-Pad42)") (class "Default")
      (node (ref "U2") (pin "42") (pinfunction "RPF5/SCL5/PMA8/RF5_42") (pintype "passive"))
    )
    (net (code "68") (name "unconnected-(U2-TCK{slash}AN7{slash}PMA11{slash}RB12-Pad27)") (class "Default")
      (node (ref "U2") (pin "27") (pinfunction "TCK/AN7/PMA11/RB12_27") (pintype "passive"))
    )
    (net (code "69") (name "unconnected-(U2-TDI{slash}AN8{slash}RB13-Pad28)") (class "Default")
      (node (ref "U2") (pin "28") (pinfunction "TDI/AN8/RB13_28") (pintype "passive"))
    )
    (net (code "70") (name "unconnected-(U2-TRCLK{slash}SQICLK{slash}ERXD2{slash}AETXD0{slash}RPF1{slash}RF1-Pad57)") (class "Default")
      (node (ref "U2") (pin "57") (pinfunction "TRCLK/SQICLK/ERXD2/AETXD0/RPF1/RF1_57") (pintype "passive"))
    )
    (net (code "71") (name "unconnected-(U2-TRD0{slash}SQID0{slash}ERXD1{slash}PMD0{slash}RE0-Pad58)") (class "Default")
      (node (ref "U2") (pin "58") (pinfunction "TRD0/SQID0/ERXD1/PMD0/RE0_58") (pintype "passive"))
    )
    (net (code "72") (name "unconnected-(U2-TRD1{slash}SQID1{slash}ERXD0{slash}PMD1{slash}RE1-Pad61)") (class "Default")
      (node (ref "U2") (pin "61") (pinfunction "TRD1/SQID1/ERXD0/PMD1/RE1_61") (pintype "passive"))
    )
    (net (code "73") (name "unconnected-(U2-TRD3{slash}SQID3{slash}ERXCLK{slash}EREFCLK{slash}RPE3{slash}PMD3{slash}RE3-Pad63)") (class "Default")
      (node (ref "U2") (pin "63") (pinfunction "TRD3/SQID3/ERXCLK/EREFCLK/RPE3/PMD3/RE3_63") (pintype "passive"))
    )
    (net (code "74") (name "unconnected-(U2-_TRD2{slash}SQID2{slash}ERXDV{slash}ECRSDV{slash}AECRSDV{slash}PMD2{slash}RE2-Pad62)") (class "Default")
      (node (ref "U2") (pin "62") (pinfunction "_TRD2/SQID2/ERXDV/ECRSDV/AECRSDV/PMD2/RE2_62") (pintype "passive"))
    )
    (net (code "75") (name "unconnected-(U5-CS_A{slash}G-Pad7)") (class "Default")
      (node (ref "U5") (pin "7") (pinfunction "CS_A/G_7") (pintype "input+no_connect"))
    )
    (net (code "76") (name "unconnected-(U5-CS_M-Pad8)") (class "Default")
      (node (ref "U5") (pin "8") (pinfunction "CS_M_8") (pintype "input+no_connect"))
    )
    (net (code "77") (name "unconnected-(U5-DEN_A{slash}G-Pad13)") (class "Default")
      (node (ref "U5") (pin "13") (pinfunction "DEN_A/G_13") (pintype "input+no_connect"))
    )
    (net (code "78") (name "unconnected-(U5-DRDY_M-Pad9)") (class "Default")
      (node (ref "U5") (pin "9") (pinfunction "DRDY_M_9") (pintype "output+no_connect"))
    )
    (net (code "79") (name "unconnected-(U5-INT1_A{slash}G-Pad11)") (class "Default")
      (node (ref "U5") (pin "11") (pinfunction "INT1_A/G_11") (pintype "output+no_connect"))
    )
    (net (code "80") (name "unconnected-(U5-INT2_A{slash}G-Pad12)") (class "Default")
      (node (ref "U5") (pin "12") (pinfunction "INT2_A/G_12") (pintype "output+no_connect"))
    )
    (net (code "81") (name "unconnected-(U5-INT_M-Pad10)") (class "Default")
      (node (ref "U5") (pin "10") (pinfunction "INT_M_10") (pintype "output+no_connect"))
    )
    (net (code "82") (name "unconnected-(U5-SDO_A{slash}G-Pad5)") (class "Default")
      (node (ref "U5") (pin "5") (pinfunction "SDO_A/G_5") (pintype "output+no_connect"))
    )
    (net (code "83") (name "unconnected-(U5-SDO_M-Pad6)") (class "Default")
      (node (ref "U5") (pin "6") (pinfunction "SDO_M_6") (pintype "output+no_connect"))
    )
  )
)
